# ife19_Elec_TS_TSAL_Light.net
KiCad netlist of a schematic drawn in Altium Designer
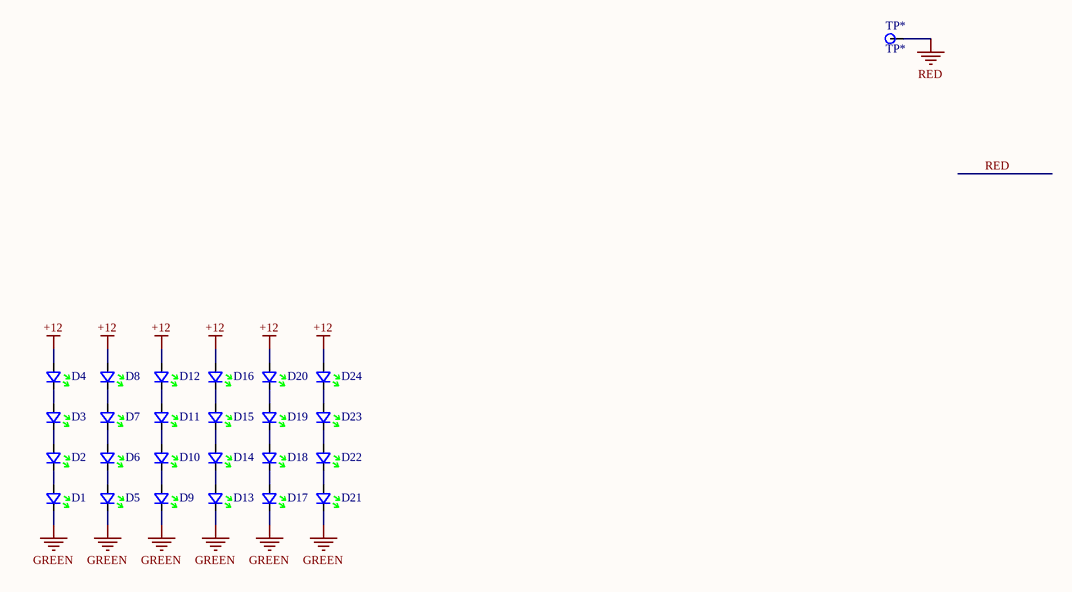
[diagram p0: ife19_Elec_TS_TSAL_Light.SchDoc]

(export (version "E")
  (design (tool "Eeschema 10.0.6"))
  (components
    (comp (ref "D1")
      (value "LEDGREEN-1806-RIGHT")
      (footprint "LEDGREEN-1806-RIGHT")
      (libsource (lib "ife19_Elec_Library") (part "LEDGREEN-1806-RIGHT"))
    )
    (comp (ref "D2")
      (value "LEDGREEN-1806-RIGHT")
      (footprint "LEDGREEN-1806-RIGHT")
      (libsource (lib "ife19_Elec_Library") (part "LEDGREEN-1806-RIGHT"))
    )
    (comp (ref "D3")
      (value "LEDGREEN-1806-RIGHT")
      (footprint "LEDGREEN-1806-RIGHT")
      (libsource (lib "ife19_Elec_Library") (part "LEDGREEN-1806-RIGHT"))
    )
    (comp (ref "D4")
      (value "LEDGREEN-1806-RIGHT")
      (footprint "LEDGREEN-1806-RIGHT")
      (libsource (lib "ife19_Elec_Library") (part "LEDGREEN-1806-RIGHT"))
    )
    (comp (ref "D5")
      (value "LEDGREEN-1806-RIGHT")
      (footprint "LEDGREEN-1806-RIGHT")
      (libsource (lib "ife19_Elec_Library") (part "LEDGREEN-1806-RIGHT"))
    )
    (comp (ref "D6")
      (value "LEDGREEN-1806-RIGHT")
      (footprint "LEDGREEN-1806-RIGHT")
      (libsource (lib "ife19_Elec_Library") (part "LEDGREEN-1806-RIGHT"))
    )
    (comp (ref "D7")
      (value "LEDGREEN-1806-RIGHT")
      (footprint "LEDGREEN-1806-RIGHT")
      (libsource (lib "ife19_Elec_Library") (part "LEDGREEN-1806-RIGHT"))
    )
    (comp (ref "D8")
      (value "LEDGREEN-1806-RIGHT")
      (footprint "LEDGREEN-1806-RIGHT")
      (libsource (lib "ife19_Elec_Library") (part "LEDGREEN-1806-RIGHT"))
    )
    (comp (ref "D9")
      (value "LEDGREEN-1806-RIGHT")
      (footprint "LEDGREEN-1806-RIGHT")
      (libsource (lib "ife19_Elec_Library") (part "LEDGREEN-1806-RIGHT"))
    )
    (comp (ref "D10")
      (value "LEDGREEN-1806-RIGHT")
      (footprint "LEDGREEN-1806-RIGHT")
      (libsource (lib "ife19_Elec_Library") (part "LEDGREEN-1806-RIGHT"))
    )
    (comp (ref "D11")
      (value "LEDGREEN-1806-RIGHT")
      (footprint "LEDGREEN-1806-RIGHT")
      (libsource (lib "ife19_Elec_Library") (part "LEDGREEN-1806-RIGHT"))
    )
    (comp (ref "D12")
      (value "LEDGREEN-1806-RIGHT")
      (footprint "LEDGREEN-1806-RIGHT")
      (libsource (lib "ife19_Elec_Library") (part "LEDGREEN-1806-RIGHT"))
    )
    (comp (ref "D13")
      (value "LEDGREEN-1806-RIGHT")
      (footprint "LEDGREEN-1806-RIGHT")
      (libsource (lib "ife19_Elec_Library") (part "LEDGREEN-1806-RIGHT"))
    )
    (comp (ref "D14")
      (value "LEDGREEN-1806-RIGHT")
      (footprint "LEDGREEN-1806-RIGHT")
      (libsource (lib "ife19_Elec_Library") (part "LEDGREEN-1806-RIGHT"))
    )
    (comp (ref "D15")
      (value "LEDGREEN-1806-RIGHT")
      (footprint "LEDGREEN-1806-RIGHT")
      (libsource (lib "ife19_Elec_Library") (part "LEDGREEN-1806-RIGHT"))
    )
    (comp (ref "D16")
      (value "LEDGREEN-1806-RIGHT")
      (footprint "LEDGREEN-1806-RIGHT")
      (libsource (lib "ife19_Elec_Library") (part "LEDGREEN-1806-RIGHT"))
    )
    (comp (ref "D17")
      (value "LEDGREEN-1806-RIGHT")
      (footprint "LEDGREEN-1806-RIGHT")
      (libsource (lib "ife19_Elec_Library") (part "LEDGREEN-1806-RIGHT"))
    )
    (comp (ref "D18")
      (value "LEDGREEN-1806-RIGHT")
      (footprint "LEDGREEN-1806-RIGHT")
      (libsource (lib "ife19_Elec_Library") (part "LEDGREEN-1806-RIGHT"))
    )
    (comp (ref "D19")
      (value "LEDGREEN-1806-RIGHT")
      (footprint "LEDGREEN-1806-RIGHT")
      (libsource (lib "ife19_Elec_Library") (part "LEDGREEN-1806-RIGHT"))
    )
    (comp (ref "D20")
      (value "LEDGREEN-1806-RIGHT")
      (footprint "LEDGREEN-1806-RIGHT")
      (libsource (lib "ife19_Elec_Library") (part "LEDGREEN-1806-RIGHT"))
    )
    (comp (ref "D21")
      (value "LEDGREEN-1806-RIGHT")
      (footprint "LEDGREEN-1806-RIGHT")
      (libsource (lib "ife19_Elec_Library") (part "LEDGREEN-1806-RIGHT"))
    )
    (comp (ref "D22")
      (value "LEDGREEN-1806-RIGHT")
      (footprint "LEDGREEN-1806-RIGHT")
      (libsource (lib "ife19_Elec_Library") (part "LEDGREEN-1806-RIGHT"))
    )
    (comp (ref "D23")
      (value "LEDGREEN-1806-RIGHT")
      (footprint "LEDGREEN-1806-RIGHT")
      (libsource (lib "ife19_Elec_Library") (part "LEDGREEN-1806-RIGHT"))
    )
    (comp (ref "D24")
      (value "LEDGREEN-1806-RIGHT")
      (footprint "LEDGREEN-1806-RIGHT")
      (libsource (lib "ife19_Elec_Library") (part "LEDGREEN-1806-RIGHT"))
    )
    (comp (ref "TP*")
      (value "TP*")
      (footprint "Testpoint")
      (libsource (lib "ife19_Elec_Library") (part "Testpoint"))
    )
  )
  (nets
    (net (code "1") (name "+12") (class "Default")
      (node (ref "D12") (pin "A") (pinfunction "A_A") (pintype "passive"))
      (node (ref "D16") (pin "A") (pinfunction "A_A") (pintype "passive"))
      (node (ref "D20") (pin "A") (pinfunction "A_A") (pintype "passive"))
      (node (ref "D24") (pin "A") (pinfunction "A_A") (pintype "passive"))
      (node (ref "D4") (pin "A") (pinfunction "A_A") (pintype "passive"))
      (node (ref "D8") (pin "A") (pinfunction "A_A") (pintype "passive"))
    )
    (net (code "2") (name "GREEN") (class "Default")
      (node (ref "D1") (pin "K") (pinfunction "K_K") (pintype "passive"))
      (node (ref "D13") (pin "K") (pinfunction "K_K") (pintype "passive"))
      (node (ref "D17") (pin "K") (pinfunction "K_K") (pintype "passive"))
      (node (ref "D21") (pin "K") (pinfunction "K_K") (pintype "passive"))
      (node (ref "D5") (pin "K") (pinfunction "K_K") (pintype "passive"))
      (node (ref "D9") (pin "K") (pinfunction "K_K") (pintype "passive"))
    )
    (net (code "3") (name "Net-(D1-PadA)") (class "Default")
      (node (ref "D1") (pin "A") (pinfunction "A_A") (pintype "passive"))
      (node (ref "D2") (pin "K") (pinfunction "K_K") (pintype "passive"))
    )
    (net (code "4") (name "Net-(D2-PadA)") (class "Default")
      (node (ref "D2") (pin "A") (pinfunction "A_A") (pintype "passive"))
      (node (ref "D3") (pin "K") (pinfunction "K_K") (pintype "passive"))
    )
    (net (code "5") (name "Net-(D3-PadA)") (class "Default")
      (node (ref "D3") (pin "A") (pinfunction "A_A") (pintype "passive"))
      (node (ref "D4") (pin "K") (pinfunction "K_K") (pintype "passive"))
    )
    (net (code "6") (name "Net-(D5-PadA)") (class "Default")
      (node (ref "D5") (pin "A") (pinfunction "A_A") (pintype "passive"))
      (node (ref "D6") (pin "K") (pinfunction "K_K") (pintype "passive"))
    )
    (net (code "7") (name "Net-(D6-PadA)") (class "Default")
      (node (ref "D6") (pin "A") (pinfunction "A_A") (pintype "passive"))
      (node (ref "D7") (pin "K") (pinfunction "K_K") (pintype "passive"))
    )
    (net (code "8") (name "Net-(D7-PadA)") (class "Default")
      (node (ref "D7") (pin "A") (pinfunction "A_A") (pintype "passive"))
      (node (ref "D8") (pin "K") (pinfunction "K_K") (pintype "passive"))
    )
    (net (code "9") (name "Net-(D10-PadA)") (class "Default")
      (node (ref "D10") (pin "A") (pinfunction "A_A") (pintype "passive"))
      (node (ref "D11") (pin "K") (pinfunction "K_K") (pintype "passive"))
    )
    (net (code "10") (name "Net-(D10-PadK)") (class "Default")
      (node (ref "D10") (pin "K") (pinfunction "K_K") (pintype "passive"))
      (node (ref "D9") (pin "A") (pinfunction "A_A") (pintype "passive"))
    )
    (net (code "11") (name "Net-(D11-PadA)") (class "Default")
      (node (ref "D11") (pin "A") (pinfunction "A_A") (pintype "passive"))
      (node (ref "D12") (pin "K") (pinfunction "K_K") (pintype "passive"))
    )
    (net (code "12") (name "Net-(D13-PadA)") (class "Default")
      (node (ref "D13") (pin "A") (pinfunction "A_A") (pintype "passive"))
      (node (ref "D14") (pin "K") (pinfunction "K_K") (pintype "passive"))
    )
    (net (code "13") (name "Net-(D14-PadA)") (class "Default")
      (node (ref "D14") (pin "A") (pinfunction "A_A") (pintype "passive"))
      (node (ref "D15") (pin "K") (pinfunction "K_K") (pintype "passive"))
    )
    (net (code "14") (name "Net-(D15-PadA)") (class "Default")
      (node (ref "D15") (pin "A") (pinfunction "A_A") (pintype "passive"))
      (node (ref "D16") (pin "K") (pinfunction "K_K") (pintype "passive"))
    )
    (net (code "15") (name "Net-(D17-PadA)") (class "Default")
      (node (ref "D17") (pin "A") (pinfunction "A_A") (pintype "passive"))
      (node (ref "D18") (pin "K") (pinfunction "K_K") (pintype "passive"))
    )
    (net (code "16") (name "Net-(D18-PadA)") (class "Default")
      (node (ref "D18") (pin "A") (pinfunction "A_A") (pintype "passive"))
      (node (ref "D19") (pin "K") (pinfunction "K_K") (pintype "passive"))
    )
    (net (code "17") (name "Net-(D19-PadA)") (class "Default")
      (node (ref "D19") (pin "A") (pinfunction "A_A") (pintype "passive"))
      (node (ref "D20") (pin "K") (pinfunction "K_K") (pintype "passive"))
    )
    (net (code "18") (name "Net-(D21-PadA)") (class "Default")
      (node (ref "D21") (pin "A") (pinfunction "A_A") (pintype "passive"))
      (node (ref "D22") (pin "K") (pinfunction "K_K") (pintype "passive"))
    )
    (net (code "19") (name "Net-(D22-PadA)") (class "Default")
      (node (ref "D22") (pin "A") (pinfunction "A_A") (pintype "passive"))
      (node (ref "D23") (pin "K") (pinfunction "K_K") (pintype "passive"))
    )
    (net (code "20") (name "Net-(D23-PadA)") (class "Default")
      (node (ref "D23") (pin "A") (pinfunction "A_A") (pintype "passive"))
      (node (ref "D24") (pin "K") (pinfunction "K_K") (pintype "passive"))
    )
    (net (code "21") (name "RED") (class "Default")
      (node (ref "TP*") (pin "1") (pinfunction "1_1") (pintype "passive"))
    )
  )
)
